# iTag3.net
KiCad netlist of a schematic drawn in Altium Designer
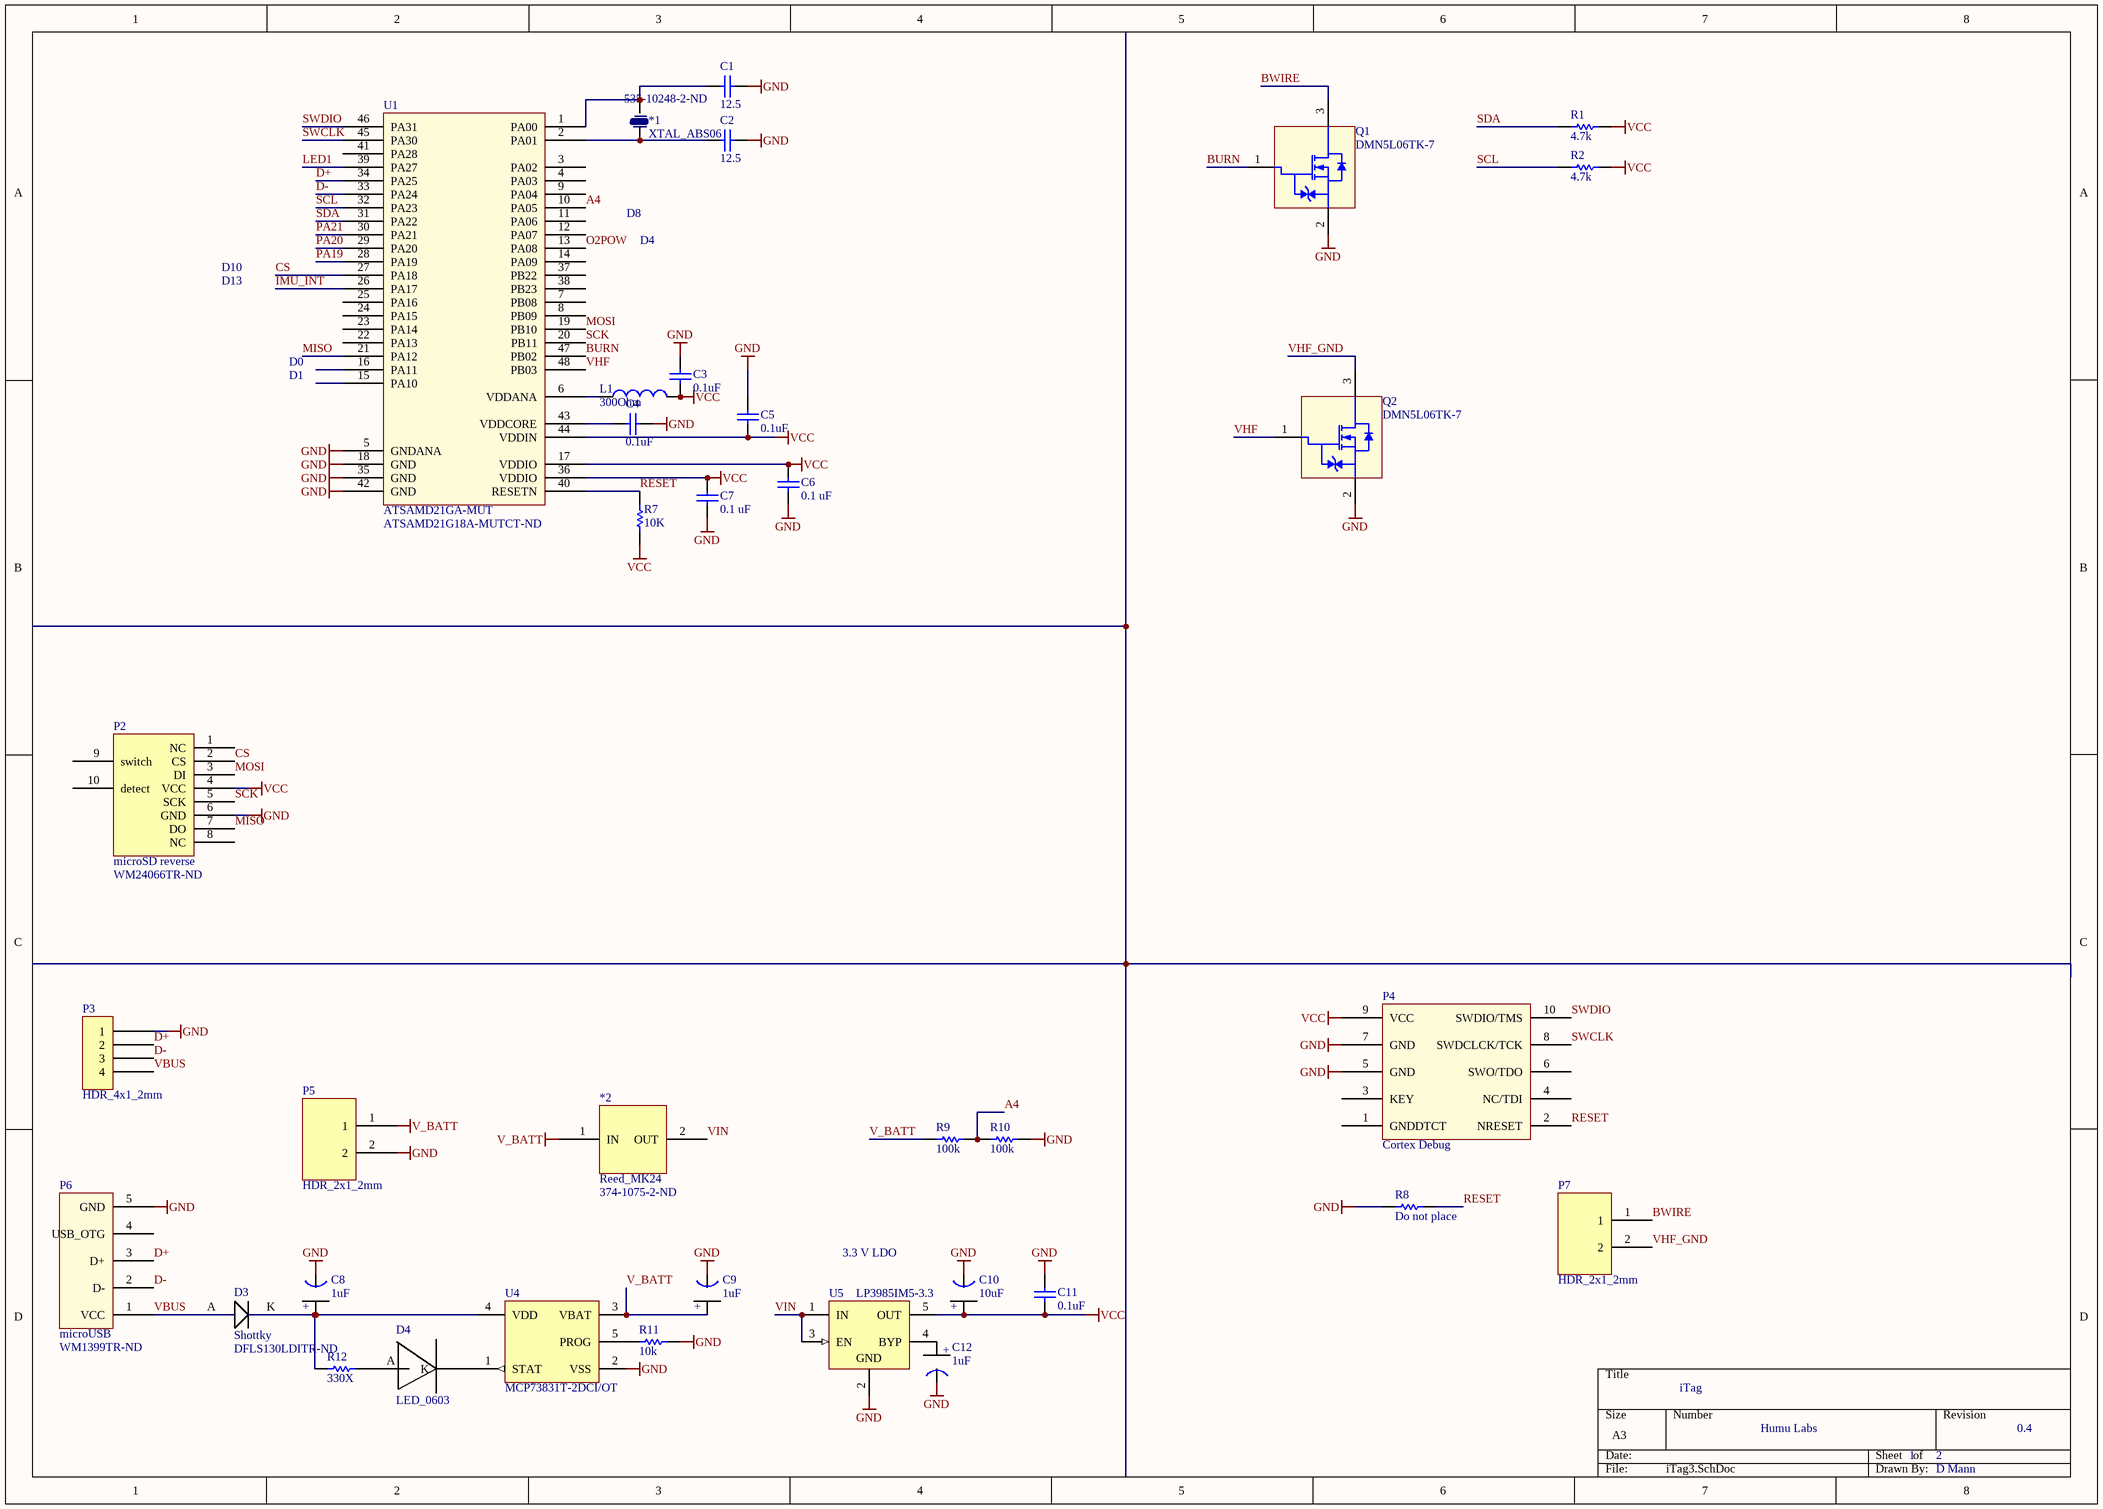
[diagram p0: iTag3.SchDoc]

(export (version "E")
  (design (tool "Eeschema 10.0.6"))
  (components
    (comp (ref "*1")
      (value "XTAL_ABS06")
      (footprint "XTAL-ABS06")
      (fields (field (name "SUPPLIER PART NUMBER 1") "535-10248-2-ND"))
      (libsource (lib "Loggerhead") (part "XTAL_ABS06"))
    )
    (comp (ref "*2")
      (value "Reed_MK24")
      (footprint "Reed MK24-B-3")
      (fields (field (name "SUPPLIER PART NUMBER 1") "374-1075-2-ND"))
      (libsource (lib "Loggerhead") (part "Reed_MK24"))
    )
    (comp (ref "C1")
      (value "12.5")
      (footprint "0402")
      (description "Ceramic Chip Capacitor - Standard")
      (fields (field (name "PUBLISHER") "Altium Limited"))
      (libsource (lib "KEMET Chip Capacitor") (part "C0402"))
    )
    (comp (ref "C2")
      (value "12.5")
      (footprint "0402")
      (description "Ceramic Chip Capacitor - Standard")
      (fields (field (name "PUBLISHER") "Altium Limited"))
      (libsource (lib "KEMET Chip Capacitor") (part "C0402"))
    )
    (comp (ref "C3")
      (value "0.1uF")
      (footprint "0402")
      (description "Ceramic Chip Capacitor - Standard")
      (fields (field (name "PUBLISHER") "Altium Limited"))
      (libsource (lib "KEMET Chip Capacitor") (part "C0402"))
    )
    (comp (ref "C4")
      (value "0.1uF")
      (footprint "0402")
      (description "Ceramic Chip Capacitor - Standard")
      (fields (field (name "PUBLISHER") "Altium Limited"))
      (libsource (lib "KEMET Chip Capacitor") (part "C0402"))
    )
    (comp (ref "C5")
      (value "0.1uF")
      (footprint "0402")
      (description "Ceramic Chip Capacitor - Standard")
      (fields (field (name "PUBLISHER") "Altium Limited"))
      (libsource (lib "KEMET Chip Capacitor") (part "C0402"))
    )
    (comp (ref "C6")
      (value "0.1 uF")
      (footprint "0402")
      (description "Ceramic Chip Capacitor - Standard")
      (fields (field (name "PUBLISHER") "Altium Limited"))
      (libsource (lib "KEMET Chip Capacitor") (part "C0402"))
    )
    (comp (ref "C7")
      (value "0.1 uF")
      (footprint "0402")
      (description "Ceramic Chip Capacitor - Standard")
      (fields (field (name "PUBLISHER") "Altium Limited"))
      (libsource (lib "KEMET Chip Capacitor") (part "C0402"))
    )
    (comp (ref "C8") (value "1uF") (footprint "Tant0805") (libsource (lib "Loggerhead") (part "Tant0805")))
    (comp (ref "C9") (value "1uF") (footprint "Tant0805") (libsource (lib "Loggerhead") (part "Tant0805")))
    (comp (ref "C10") (value "10uF") (footprint "Tant0805") (libsource (lib "Loggerhead") (part "Tant0805")))
    (comp (ref "C11")
      (value "0.1uF")
      (footprint "0402")
      (description "Ceramic Chip Capacitor - Standard")
      (fields (field (name "PUBLISHER") "Altium Limited"))
      (libsource (lib "KEMET Chip Capacitor") (part "C0402"))
    )
    (comp (ref "C12") (value "1uF") (footprint "Tant0805") (libsource (lib "Loggerhead") (part "Tant0805")))
    (comp (ref "D3")
      (value "Shottky")
      (footprint "DFLS130")
      (fields (field (name "SUPPLIER PART NUMBER 1") "DFLS130LDITR-ND"))
      (libsource (lib "Loggerhead") (part "DFLS130"))
    )
    (comp (ref "D4")
      (value "LED_0603")
      (footprint "Diode0603")
      (libsource (lib "Loggerhead") (part "LED_0603"))
    )
    (comp (ref "L1")
      (value "300Ohm")
      (footprint "0805 (M2125) Ferrite")
      (description "Ferrite 25mOhm@DC,  60 Ohm@100MHz")
      (fields
        (field (name "CREATOR AND DATE") "Design Engineer's Name")
        (field (name "FOOTPRINT VERIFIED BY") "*")
        (field (name "SCHEMATIC VERIFIED BY") "*")
        (field (name "VENDOR INFO VERIFIED BY") "*")
      )
      (libsource (lib "Flanery") (part "Ferrite 0805(M2125) 3A"))
    )
    (comp (ref "P2")
      (value "microSD reverse")
      (footprint "miroSD_reverse")
      (fields (field (name "SUPPLIER PART NUMBER 1") "WM24066TR-ND"))
      (libsource (lib "Loggerhead") (part "microSD reverse"))
    )
    (comp (ref "P3")
      (value "HDR_4x1_2mm")
      (footprint "Hdr_4x1_2mm")
      (libsource (lib "Loggerhead") (part "HDR_4x1_2mm"))
    )
    (comp (ref "P4")
      (value "Cortex Debug")
      (footprint "Header_2x5_50mil")
      (libsource (lib "Loggerhead") (part "CortexDebug"))
    )
    (comp (ref "P5")
      (value "HDR_2x1_2mm")
      (footprint "HDR_2x1_2mm")
      (libsource (lib "Loggerhead") (part "HDR_2x1_2mm"))
    )
    (comp (ref "P6")
      (value "microUSB")
      (footprint "microUSB-B")
      (fields (field (name "SUPPLIER PART NUMBER 1") "WM1399TR-ND"))
      (libsource (lib "Loggerhead") (part "microUSB-B"))
    )
    (comp (ref "P7")
      (value "HDR_2x1_2mm")
      (footprint "HDR_2x1_2mm")
      (libsource (lib "Loggerhead") (part "HDR_2x1_2mm"))
    )
    (comp (ref "Q1")
      (value "DMN5L06TK-7")
      (footprint "SOT-523")
      (description "Ultra-low leakage Enhanced MOSFET")
      (fields
        (field (name "CREATOR AND DATE") "Will Flanery 2010-09-02")
        (field (name "FOOTPRINT VERIFIED BY") "*")
        (field (name "SCHEMATIC VERIFIED BY") "*")
        (field (name "VENDOR INFO VERIFIED BY") "*")
      )
      (libsource (lib "Flanery") (part "FET DMN5L06TK-7"))
    )
    (comp (ref "Q2")
      (value "DMN5L06TK-7")
      (footprint "SOT-523")
      (description "Ultra-low leakage Enhanced MOSFET")
      (fields
        (field (name "CREATOR AND DATE") "Will Flanery 2010-09-02")
        (field (name "FOOTPRINT VERIFIED BY") "*")
        (field (name "SCHEMATIC VERIFIED BY") "*")
        (field (name "VENDOR INFO VERIFIED BY") "*")
      )
      (libsource (lib "Flanery") (part "FET DMN5L06TK-7"))
    )
    (comp (ref "R1")
      (value "4.7k")
      (footprint "3-0603")
      (fields (field (name "PUBLISHER") "Altium Limited"))
      (libsource (lib "Panasonic Resistor") (part "ERJ3RK"))
    )
    (comp (ref "R2")
      (value "4.7k")
      (footprint "3-0603")
      (fields (field (name "PUBLISHER") "Altium Limited"))
      (libsource (lib "Panasonic Resistor") (part "ERJ3RK"))
    )
    (comp (ref "R7")
      (value "10K")
      (footprint "3-0603")
      (fields (field (name "PUBLISHER") "Altium Limited"))
      (libsource (lib "Panasonic Resistor") (part "ERJ3RK"))
    )
    (comp (ref "R8")
      (value "Do not place")
      (footprint "3-0603")
      (fields (field (name "PUBLISHER") "Altium Limited"))
      (libsource (lib "Panasonic Resistor") (part "ERJ3RK"))
    )
    (comp (ref "R9")
      (value "100k")
      (footprint "3-0603")
      (fields (field (name "PUBLISHER") "Altium Limited"))
      (libsource (lib "Panasonic Resistor") (part "ERJ3RK"))
    )
    (comp (ref "R10")
      (value "100k")
      (footprint "3-0603")
      (fields (field (name "PUBLISHER") "Altium Limited"))
      (libsource (lib "Panasonic Resistor") (part "ERJ3RK"))
    )
    (comp (ref "R11")
      (value "10k")
      (footprint "3-0603")
      (fields (field (name "PUBLISHER") "Altium Limited"))
      (libsource (lib "Panasonic Resistor") (part "ERJ3RK"))
    )
    (comp (ref "R12")
      (value "330X")
      (footprint "3-0603")
      (fields (field (name "PUBLISHER") "Altium Limited"))
      (libsource (lib "Panasonic Resistor") (part "ERJ3RK"))
    )
    (comp (ref "U1")
      (value "ATSAMD21GA-MUT")
      (footprint "QFN127P600-8N")
      (fields (field (name "SUPPLIER PART NUMBER 1") "ATSAMD21G18A-MUTCT-ND"))
      (libsource (lib "Loggerhead") (part "ATSAMD21G18"))
    )
    (comp (ref "U4")
      (value "MCP73831T-2DCI/OT")
      (footprint "SOT-23-OT5_N")
      (libsource (lib "Microchip Power Management Battery Management") (part "MCP73831T-2DCI/OT"))
    )
    (comp (ref "U5")
      (value "LP3985IM5-3.3")
      (footprint "MF05A_N")
      (description "Micropower, 150mA Low-Noise Ultra Low-Dropout CMOS Voltage Regulator, 5-pin SOT-23")
      (fields
        (field (name "MANUFACTURER") "National Semiconductor")
        (field (name "PUBLISHER") "Altium Limited")
      )
      (libsource (lib "NSC LDO") (part "LP3985IM5-3.3"))
    )
  )
  (nets
    (net (code "1") (name "/A4") (class "Default")
      (node (ref "R10") (pin "2") (pinfunction "2_2") (pintype "passive"))
      (node (ref "R9") (pin "1") (pinfunction "1_1") (pintype "passive"))
      (node (ref "U1") (pin "10") (pinfunction "PA05_10") (pintype "passive"))
    )
    (net (code "2") (name "/BURN") (class "Default")
      (node (ref "Q1") (pin "1") (pinfunction "G_1") (pintype "passive"))
      (node (ref "U1") (pin "47") (pinfunction "PB02_47") (pintype "passive"))
    )
    (net (code "3") (name "/BWIRE") (class "Default")
      (node (ref "P7") (pin "1") (pinfunction "1_1") (pintype "passive"))
      (node (ref "Q1") (pin "3") (pinfunction "D_3") (pintype "passive"))
    )
    (net (code "4") (name "/CS") (class "Default")
      (node (ref "P2") (pin "2") (pinfunction "CS_2") (pintype "passive"))
      (node (ref "U1") (pin "27") (pinfunction "PA18_27") (pintype "passive"))
    )
    (net (code "5") (name "/D+") (class "Default")
      (node (ref "P3") (pin "2") (pinfunction "2_2") (pintype "passive"))
      (node (ref "P6") (pin "3") (pinfunction "D+_3") (pintype "passive"))
      (node (ref "U1") (pin "34") (pinfunction "PA25_34") (pintype "passive"))
    )
    (net (code "6") (name "/D-") (class "Default")
      (node (ref "P3") (pin "3") (pinfunction "3_3") (pintype "passive"))
      (node (ref "P6") (pin "2") (pinfunction "D-_2") (pintype "passive"))
      (node (ref "U1") (pin "33") (pinfunction "PA24_33") (pintype "passive"))
    )
    (net (code "7") (name "/IMU_INT") (class "Default")
      (node (ref "U1") (pin "26") (pinfunction "PA17_26") (pintype "passive"))
    )
    (net (code "8") (name "/LED1") (class "Default")
      (node (ref "U1") (pin "39") (pinfunction "PA27_39") (pintype "passive"))
    )
    (net (code "9") (name "/MISO") (class "Default")
      (node (ref "P2") (pin "7") (pinfunction "DO_7") (pintype "passive"))
      (node (ref "U1") (pin "21") (pinfunction "PA12_21") (pintype "passive"))
    )
    (net (code "10") (name "/MOSI") (class "Default")
      (node (ref "P2") (pin "3") (pinfunction "DI_3") (pintype "passive"))
      (node (ref "U1") (pin "19") (pinfunction "PB10_19") (pintype "passive"))
    )
    (net (code "11") (name "/O2POW") (class "Default")
      (node (ref "U1") (pin "13") (pinfunction "PA08_13") (pintype "passive"))
    )
    (net (code "12") (name "/PA19") (class "Default")
      (node (ref "U1") (pin "28") (pinfunction "PA19_28") (pintype "passive"))
    )
    (net (code "13") (name "/PA20") (class "Default")
      (node (ref "U1") (pin "29") (pinfunction "PA20_29") (pintype "passive"))
    )
    (net (code "14") (name "/PA21") (class "Default")
      (node (ref "U1") (pin "30") (pinfunction "PA21_30") (pintype "passive"))
    )
    (net (code "15") (name "/RESET") (class "Default")
      (node (ref "P4") (pin "2") (pinfunction "NRESET_2") (pintype "passive"))
      (node (ref "R7") (pin "2") (pinfunction "2_2") (pintype "passive"))
      (node (ref "R8") (pin "1") (pinfunction "1_1") (pintype "passive"))
      (node (ref "U1") (pin "40") (pinfunction "RESETN_40") (pintype "passive"))
    )
    (net (code "16") (name "/SCK") (class "Default")
      (node (ref "P2") (pin "5") (pinfunction "SCK_5") (pintype "passive"))
      (node (ref "U1") (pin "20") (pinfunction "PB11_20") (pintype "passive"))
    )
    (net (code "17") (name "/SCL") (class "Default")
      (node (ref "R2") (pin "1") (pinfunction "1_1") (pintype "passive"))
      (node (ref "U1") (pin "32") (pinfunction "PA23_32") (pintype "passive"))
    )
    (net (code "18") (name "/SDA") (class "Default")
      (node (ref "R1") (pin "2") (pinfunction "2_2") (pintype "passive"))
      (node (ref "U1") (pin "31") (pinfunction "PA22_31") (pintype "passive"))
    )
    (net (code "19") (name "/SWCLK") (class "Default")
      (node (ref "P4") (pin "8") (pinfunction "SWDCLCK/TCK_8") (pintype "passive"))
      (node (ref "U1") (pin "45") (pinfunction "PA30_45") (pintype "passive"))
    )
    (net (code "20") (name "/SWDIO") (class "Default")
      (node (ref "P4") (pin "10") (pinfunction "SWDIO/TMS_10") (pintype "passive"))
      (node (ref "U1") (pin "46") (pinfunction "PA31_46") (pintype "passive"))
    )
    (net (code "21") (name "/VBUS") (class "Default")
      (node (ref "D3") (pin "A") (pintype "passive"))
      (node (ref "P3") (pin "4") (pinfunction "4_4") (pintype "passive"))
      (node (ref "P6") (pin "1") (pinfunction "VCC_1") (pintype "passive"))
    )
    (net (code "22") (name "/VHF") (class "Default")
      (node (ref "Q2") (pin "1") (pinfunction "G_1") (pintype "passive"))
      (node (ref "U1") (pin "48") (pinfunction "PB03_48") (pintype "passive"))
    )
    (net (code "23") (name "/VHF_GND") (class "Default")
      (node (ref "P7") (pin "2") (pinfunction "2_2") (pintype "passive"))
      (node (ref "Q2") (pin "3") (pinfunction "D_3") (pintype "passive"))
    )
    (net (code "24") (name "/VIN") (class "Default")
      (node (ref "*2") (pin "2") (pinfunction "OUT_2") (pintype "passive"))
      (node (ref "U5") (pin "1") (pinfunction "IN_1") (pintype "power_in"))
      (node (ref "U5") (pin "3") (pinfunction "EN_3") (pintype "input"))
    )
    (net (code "25") (name "GND") (class "Default")
      (node (ref "C1") (pin "1") (pinfunction "1_1") (pintype "passive"))
      (node (ref "C10") (pin "1") (pinfunction "GND_1") (pintype "passive"))
      (node (ref "C11") (pin "2") (pinfunction "2_2") (pintype "passive"))
      (node (ref "C12") (pin "1") (pinfunction "GND_1") (pintype "passive"))
      (node (ref "C2") (pin "1") (pinfunction "1_1") (pintype "passive"))
      (node (ref "C3") (pin "2") (pinfunction "2_2") (pintype "passive"))
      (node (ref "C4") (pin "2") (pinfunction "2_2") (pintype "passive"))
      (node (ref "C5") (pin "2") (pinfunction "2_2") (pintype "passive"))
      (node (ref "C6") (pin "2") (pinfunction "2_2") (pintype "passive"))
      (node (ref "C7") (pin "2") (pinfunction "2_2") (pintype "passive"))
      (node (ref "C8") (pin "1") (pinfunction "GND_1") (pintype "passive"))
      (node (ref "C9") (pin "1") (pinfunction "GND_1") (pintype "passive"))
      (node (ref "P2") (pin "6") (pinfunction "GND_6") (pintype "passive"))
      (node (ref "P3") (pin "1") (pinfunction "1_1") (pintype "passive"))
      (node (ref "P4") (pin "5") (pinfunction "GND_5") (pintype "passive"))
      (node (ref "P4") (pin "7") (pinfunction "GND_7") (pintype "passive"))
      (node (ref "P5") (pin "2") (pinfunction "2_2") (pintype "passive"))
      (node (ref "P6") (pin "5") (pinfunction "GND_5") (pintype "passive"))
      (node (ref "Q1") (pin "2") (pinfunction "S_2") (pintype "passive"))
      (node (ref "Q2") (pin "2") (pinfunction "S_2") (pintype "passive"))
      (node (ref "R10") (pin "1") (pinfunction "1_1") (pintype "passive"))
      (node (ref "R11") (pin "1") (pinfunction "1_1") (pintype "passive"))
      (node (ref "R8") (pin "2") (pinfunction "2_2") (pintype "passive"))
      (node (ref "U1") (pin "18") (pinfunction "GND_18") (pintype "passive"))
      (node (ref "U1") (pin "35") (pinfunction "GND_35") (pintype "passive"))
      (node (ref "U1") (pin "42") (pinfunction "GND_42") (pintype "passive"))
      (node (ref "U1") (pin "5") (pinfunction "GNDANA_5") (pintype "passive"))
      (node (ref "U4") (pin "2") (pinfunction "VSS_2") (pintype "power_in"))
      (node (ref "U5") (pin "2") (pinfunction "GND_2") (pintype "power_in"))
    )
    (net (code "26") (name "Net-(C8-+)") (class "Default")
      (node (ref "C8") (pin "2") (pinfunction "+_2") (pintype "passive"))
      (node (ref "D3") (pin "K") (pintype "passive"))
      (node (ref "R12") (pin "1") (pinfunction "1_1") (pintype "passive"))
      (node (ref "U4") (pin "4") (pinfunction "VDD_4") (pintype "power_in"))
    )
    (net (code "27") (name "Net-(C12-+)") (class "Default")
      (node (ref "C12") (pin "2") (pinfunction "+_2") (pintype "passive"))
      (node (ref "U5") (pin "4") (pinfunction "BYP_4") (pintype "passive"))
    )
    (net (code "28") (name "Net-(D4-PadA)") (class "Default")
      (node (ref "D4") (pin "A") (pinfunction "A_A") (pintype "passive"))
      (node (ref "R12") (pin "2") (pinfunction "2_2") (pintype "passive"))
    )
    (net (code "29") (name "Net-(U1-PA00)") (class "Default")
      (node (ref "*1") (pin "2") (pinfunction "2_2") (pintype "passive"))
      (node (ref "C1") (pin "2") (pinfunction "2_2") (pintype "passive"))
      (node (ref "U1") (pin "1") (pinfunction "PA00_1") (pintype "passive"))
    )
    (net (code "30") (name "Net-(U1-PA01)") (class "Default")
      (node (ref "*1") (pin "1") (pinfunction "1_1") (pintype "passive"))
      (node (ref "C2") (pin "2") (pinfunction "2_2") (pintype "passive"))
      (node (ref "U1") (pin "2") (pinfunction "PA01_2") (pintype "passive"))
    )
    (net (code "31") (name "Net-(U1-VDDANA)") (class "Default")
      (node (ref "L1") (pin "1") (pinfunction "1_1") (pintype "passive"))
      (node (ref "U1") (pin "6") (pinfunction "VDDANA_6") (pintype "passive"))
    )
    (net (code "32") (name "Net-(U1-VDDCORE)") (class "Default")
      (node (ref "C4") (pin "1") (pinfunction "1_1") (pintype "passive"))
      (node (ref "U1") (pin "43") (pinfunction "VDDCORE_43") (pintype "passive"))
    )
    (net (code "33") (name "Net-(U4-PROG)") (class "Default")
      (node (ref "R11") (pin "2") (pinfunction "2_2") (pintype "passive"))
      (node (ref "U4") (pin "5") (pinfunction "PROG_5") (pintype "passive"))
    )
    (net (code "34") (name "Net-(U4-STAT)") (class "Default")
      (node (ref "D4") (pin "K") (pinfunction "K_K") (pintype "passive"))
      (node (ref "U4") (pin "1") (pinfunction "STAT_1") (pintype "output"))
    )
    (net (code "35") (name "VCC") (class "Default")
      (node (ref "C10") (pin "2") (pinfunction "+_2") (pintype "passive"))
      (node (ref "C11") (pin "1") (pinfunction "1_1") (pintype "passive"))
      (node (ref "C3") (pin "1") (pinfunction "1_1") (pintype "passive"))
      (node (ref "C5") (pin "1") (pinfunction "1_1") (pintype "passive"))
      (node (ref "C6") (pin "1") (pinfunction "1_1") (pintype "passive"))
      (node (ref "C7") (pin "1") (pinfunction "1_1") (pintype "passive"))
      (node (ref "L1") (pin "2") (pinfunction "2_2") (pintype "passive"))
      (node (ref "P2") (pin "4") (pinfunction "VCC_4") (pintype "passive"))
      (node (ref "P4") (pin "9") (pinfunction "VCC_9") (pintype "passive"))
      (node (ref "R1") (pin "1") (pinfunction "1_1") (pintype "passive"))
      (node (ref "R2") (pin "2") (pinfunction "2_2") (pintype "passive"))
      (node (ref "R7") (pin "1") (pinfunction "1_1") (pintype "passive"))
      (node (ref "U1") (pin "17") (pinfunction "VDDIO_17") (pintype "passive"))
      (node (ref "U1") (pin "36") (pinfunction "VDDIO_36") (pintype "passive"))
      (node (ref "U1") (pin "44") (pinfunction "VDDIN_44") (pintype "passive"))
      (node (ref "U5") (pin "5") (pinfunction "OUT_5") (pintype "power_in"))
    )
    (net (code "36") (name "V_BATT") (class "Default")
      (node (ref "*2") (pin "1") (pinfunction "IN_1") (pintype "passive"))
      (node (ref "C9") (pin "2") (pinfunction "+_2") (pintype "passive"))
      (node (ref "P5") (pin "1") (pinfunction "1_1") (pintype "passive"))
      (node (ref "R9") (pin "2") (pinfunction "2_2") (pintype "passive"))
      (node (ref "U4") (pin "3") (pinfunction "VBAT_3") (pintype "power_in"))
    )
    (net (code "37") (name "unconnected-(P2-NC-Pad1)") (class "Default")
      (node (ref "P2") (pin "1") (pinfunction "NC_1") (pintype "passive"))
    )
    (net (code "38") (name "unconnected-(P2-NC-Pad8)") (class "Default")
      (node (ref "P2") (pin "8") (pinfunction "NC_8") (pintype "passive"))
    )
    (net (code "39") (name "unconnected-(P2-detect-Pad10)") (class "Default")
      (node (ref "P2") (pin "10") (pinfunction "detect_10") (pintype "passive"))
    )
    (net (code "40") (name "unconnected-(P2-switch-Pad9)") (class "Default")
      (node (ref "P2") (pin "9") (pinfunction "switch_9") (pintype "passive"))
    )
    (net (code "41") (name "unconnected-(P4-GNDDTCT-Pad1)") (class "Default")
      (node (ref "P4") (pin "1") (pinfunction "GNDDTCT_1") (pintype "passive"))
    )
    (net (code "42") (name "unconnected-(P4-KEY-Pad3)") (class "Default")
      (node (ref "P4") (pin "3") (pinfunction "KEY_3") (pintype "passive"))
    )
    (net (code "43") (name "unconnected-(P4-NC{slash}TDI-Pad4)") (class "Default")
      (node (ref "P4") (pin "4") (pinfunction "NC/TDI_4") (pintype "passive"))
    )
    (net (code "44") (name "unconnected-(P4-SWO{slash}TDO-Pad6)") (class "Default")
      (node (ref "P4") (pin "6") (pinfunction "SWO/TDO_6") (pintype "passive"))
    )
    (net (code "45") (name "unconnected-(P6-USB_OTG-Pad4)") (class "Default")
      (node (ref "P6") (pin "4") (pinfunction "USB_OTG_4") (pintype "passive"))
    )
    (net (code "46") (name "unconnected-(U1-PA02-Pad3)") (class "Default")
      (node (ref "U1") (pin "3") (pinfunction "PA02_3") (pintype "passive"))
    )
    (net (code "47") (name "unconnected-(U1-PA03-Pad4)") (class "Default")
      (node (ref "U1") (pin "4") (pinfunction "PA03_4") (pintype "passive"))
    )
    (net (code "48") (name "unconnected-(U1-PA04-Pad9)") (class "Default")
      (node (ref "U1") (pin "9") (pinfunction "PA04_9") (pintype "passive"))
    )
    (net (code "49") (name "unconnected-(U1-PA06-Pad11)") (class "Default")
      (node (ref "U1") (pin "11") (pinfunction "PA06_11") (pintype "passive"))
    )
    (net (code "50") (name "unconnected-(U1-PA07-Pad12)") (class "Default")
      (node (ref "U1") (pin "12") (pinfunction "PA07_12") (pintype "passive"))
    )
    (net (code "51") (name "unconnected-(U1-PA09-Pad14)") (class "Default")
      (node (ref "U1") (pin "14") (pinfunction "PA09_14") (pintype "passive"))
    )
    (net (code "52") (name "unconnected-(U1-PA10-Pad15)") (class "Default")
      (node (ref "U1") (pin "15") (pinfunction "PA10_15") (pintype "passive"))
    )
    (net (code "53") (name "unconnected-(U1-PA11-Pad16)") (class "Default")
      (node (ref "U1") (pin "16") (pinfunction "PA11_16") (pintype "passive"))
    )
    (net (code "54") (name "unconnected-(U1-PA13-Pad22)") (class "Default")
      (node (ref "U1") (pin "22") (pinfunction "PA13_22") (pintype "passive"))
    )
    (net (code "55") (name "unconnected-(U1-PA14-Pad23)") (class "Default")
      (node (ref "U1") (pin "23") (pinfunction "PA14_23") (pintype "passive"))
    )
    (net (code "56") (name "unconnected-(U1-PA15-Pad24)") (class "Default")
      (node (ref "U1") (pin "24") (pinfunction "PA15_24") (pintype "passive"))
    )
    (net (code "57") (name "unconnected-(U1-PA16-Pad25)") (class "Default")
      (node (ref "U1") (pin "25") (pinfunction "PA16_25") (pintype "passive"))
    )
    (net (code "58") (name "unconnected-(U1-PA28-Pad41)") (class "Default")
      (node (ref "U1") (pin "41") (pinfunction "PA28_41") (pintype "passive"))
    )
    (net (code "59") (name "unconnected-(U1-PB08-Pad7)") (class "Default")
      (node (ref "U1") (pin "7") (pinfunction "PB08_7") (pintype "passive"))
    )
    (net (code "60") (name "unconnected-(U1-PB09-Pad8)") (class "Default")
      (node (ref "U1") (pin "8") (pinfunction "PB09_8") (pintype "passive"))
    )
    (net (code "61") (name "unconnected-(U1-PB22-Pad37)") (class "Default")
      (node (ref "U1") (pin "37") (pinfunction "PB22_37") (pintype "passive"))
    )
    (net (code "62") (name "unconnected-(U1-PB23-Pad38)") (class "Default")
      (node (ref "U1") (pin "38") (pinfunction "PB23_38") (pintype "passive"))
    )
  )
)
